# seeds.net
KiCad netlist of a schematic drawn in Altium Designer
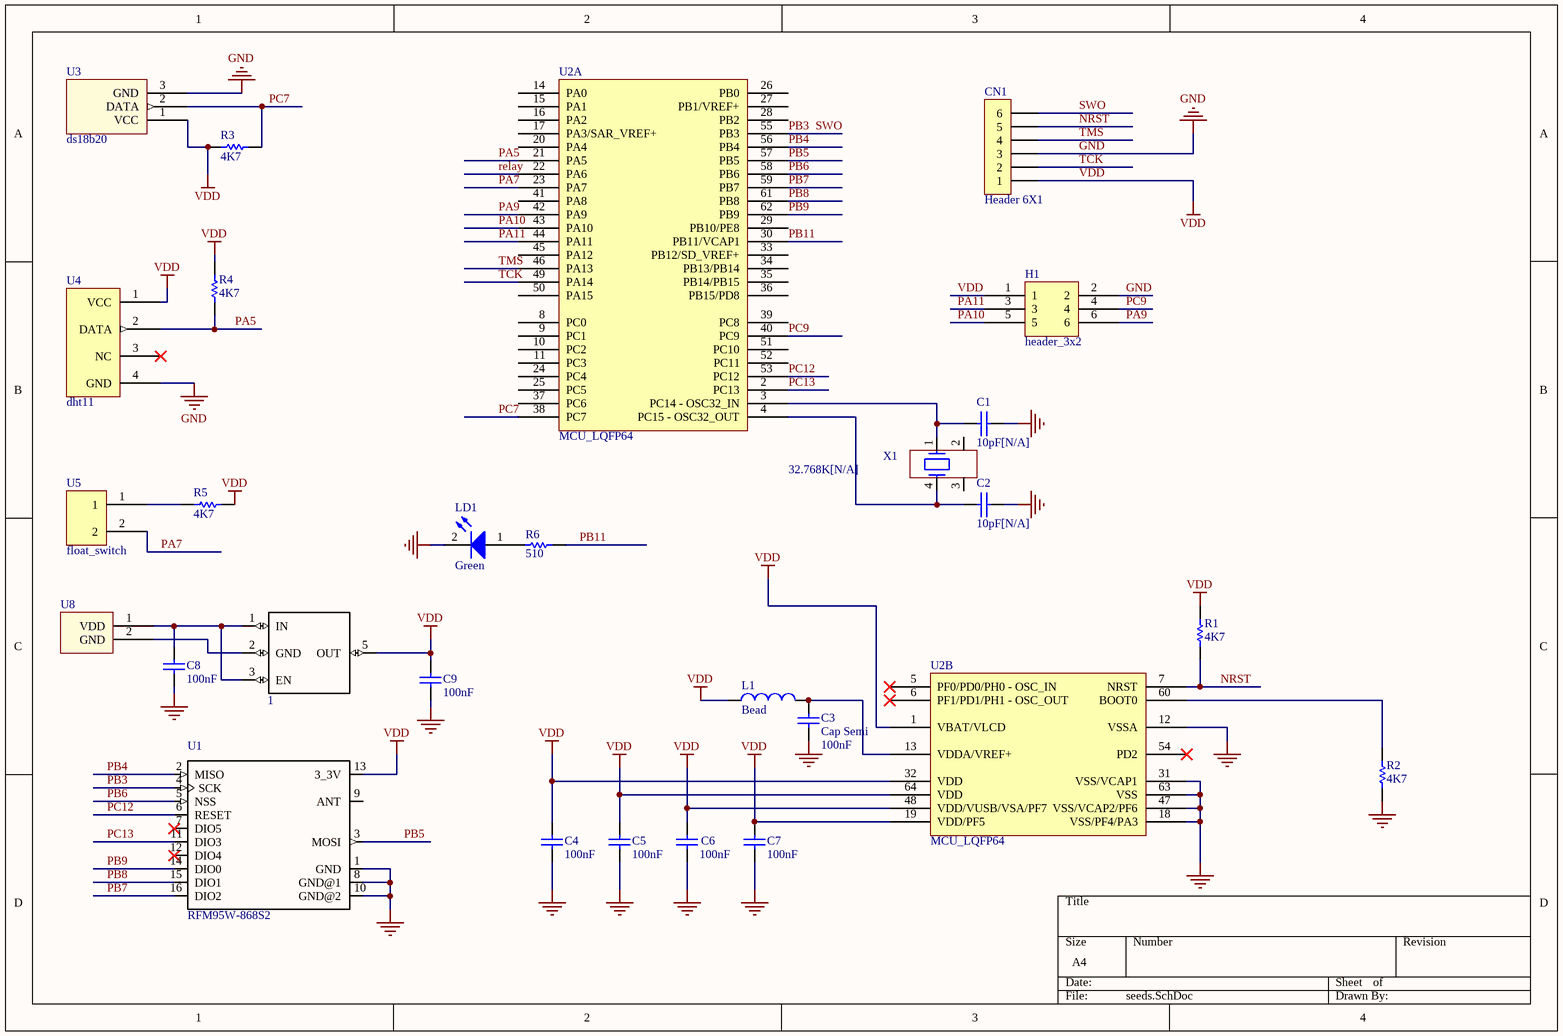
[diagram p0: seeds.SchDoc]

(export (version "E")
  (design (tool "Eeschema 10.0.6"))
  (components
    (comp (ref "1")
      (value "TLV70233DBVR")
      (footprint "SOT23-5")
      (description "LDO voltage regulator [Texas Instruments] TLV70233DBVR LDO voltage regulator")
      (fields (field (name "MF") "Texas Instruments"))
      (libsource (lib "TLV70233DBVR") (part "TLV70233DBVR"))
    )
    (comp (ref "C1")
      (value "10pF[N/A]")
      (footprint "0603C")
      (description "Capacitor")
      (libsource (lib "MB1136") (part "CAP"))
    )
    (comp (ref "C2")
      (value "10pF[N/A]")
      (footprint "0603C")
      (description "Capacitor")
      (libsource (lib "*") (part "CAP"))
    )
    (comp (ref "C3")
      (value "Cap Semi")
      (footprint "1608[0603]")
      (description "Capacitor (Semiconductor SIM Model)")
      (fields (field (name "ALTIUM_VALUE") "100nF") (field (name "PUBLISHER") "Altium Limited"))
      (libsource (lib "Miscellaneous Devices") (part "Cap Semi"))
    )
    (comp (ref "C4")
      (value "100nF")
      (footprint "0603C")
      (description "Capacitor")
      (fields (field (name "PUBLISHER") "Altium Limited"))
      (libsource (lib "Miscellaneous Devices") (part "Cap"))
    )
    (comp (ref "C5")
      (value "100nF")
      (footprint "0603C")
      (description "Capacitor")
      (fields (field (name "PUBLISHER") "Altium Limited"))
      (libsource (lib "Miscellaneous Devices") (part "Cap"))
    )
    (comp (ref "C6")
      (value "100nF")
      (footprint "0603C")
      (description "Capacitor")
      (fields (field (name "PUBLISHER") "Altium Limited"))
      (libsource (lib "Miscellaneous Devices") (part "Cap"))
    )
    (comp (ref "C7")
      (value "100nF")
      (footprint "0603C")
      (description "Capacitor")
      (fields (field (name "PUBLISHER") "Altium Limited"))
      (libsource (lib "Miscellaneous Devices") (part "Cap"))
    )
    (comp (ref "C8")
      (value "100nF")
      (footprint "0603C")
      (description "Capacitor")
      (fields (field (name "PUBLISHER") "Altium Limited"))
      (libsource (lib "Miscellaneous Devices") (part "Cap"))
    )
    (comp (ref "C9")
      (value "100nF")
      (footprint "0603C")
      (description "Capacitor")
      (fields (field (name "PUBLISHER") "Altium Limited"))
      (libsource (lib "Miscellaneous Devices") (part "Cap"))
    )
    (comp (ref "CN1")
      (value "Header 6X1")
      (footprint "1*6P")
      (description "Header, 6-Pin, Single row")
      (fields (field (name "PUBLISHER") "Altium Limited"))
      (libsource (lib "MB1136") (part "Header 6X1"))
    )
    (comp (ref "H1")
      (value "header_3x2")
      (footprint "header_3x2")
      (libsource (lib "seeds") (part "header_3x2"))
    )
    (comp (ref "L1")
      (value "Bead")
      (footprint "INDC1608L")
      (description "Inductor")
      (fields (field (name "PUBLISHER") "Altium Limited"))
      (libsource (lib "Miscellaneous Devices") (part "Inductor"))
    )
    (comp (ref "LD1")
      (value "Green")
      (footprint "0603D")
      (description "Typical RED, GREEN, YELLOW, AMBER GaAs LED")
      (fields (field (name "PUBLISHER") "Altium Limited"))
      (libsource (lib "Miscellaneous Devices") (part "LED2"))
    )
    (comp (ref "R1")
      (value "4K7")
      (footprint "0603R")
      (description "Resistor")
      (fields (field (name "PUBLISHER") "Altium Limited"))
      (libsource (lib "MB1136") (part "Res1"))
    )
    (comp (ref "R2")
      (value "4K7")
      (footprint "0603R")
      (description "Resistor")
      (fields (field (name "PUBLISHER") "Altium Limited"))
      (libsource (lib "MB1136") (part "Res1"))
    )
    (comp (ref "R3")
      (value "4K7")
      (footprint "0603R")
      (description "Resistor")
      (fields (field (name "PUBLISHER") "Altium Limited"))
      (libsource (lib "MB1136") (part "Res1"))
    )
    (comp (ref "R4")
      (value "4K7")
      (footprint "0603R")
      (description "Resistor")
      (fields (field (name "PUBLISHER") "Altium Limited"))
      (libsource (lib "MB1136") (part "Res1"))
    )
    (comp (ref "R5")
      (value "4K7")
      (footprint "0603R")
      (description "Resistor")
      (fields (field (name "PUBLISHER") "Altium Limited"))
      (libsource (lib "MB1136") (part "Res1"))
    )
    (comp (ref "R6")
      (value "510")
      (footprint "0603R")
      (description "Resistor")
      (fields (field (name "PUBLISHER") "Altium Limited"))
      (libsource (lib "Miscellaneous Devices") (part "Res1"))
    )
    (comp (ref "U1")
      (value "RFM95W-868S2")
      (footprint "XCVR_RFM95W-868S2")
      (fields (field (name "MF") "Hope Microelectronics"))
      (libsource (lib "RFM95W-868S2") (part "RFM95W-868S2"))
    )
    (comp (ref "U2") (value "MCU_LQFP64") (footprint "LQFP64") (libsource (lib "MB1136") (part "MCU_LQFP64")))
    (comp (ref "U3") (value "ds18b20") (footprint "ds18b20") (libsource (lib "seeds") (part "ds18b20")))
    (comp (ref "U4") (value "dht11") (footprint "seeds:dht11") (libsource (lib "seeds") (part "dht11")))
    (comp (ref "U5")
      (value "float_switch")
      (footprint "float_switch")
      (libsource (lib "seeds") (part "float_switch"))
    )
    (comp (ref "U8")
      (value "BATTERY_CONNECTOR")
      (footprint "BATTERY_CONNECTOR")
      (libsource (lib "seeds") (part "BATTERY_CONNECTOR"))
    )
    (comp (ref "X1") (value "32.768K[N/A]") (footprint "XTAL_4SM_8X3R8") (libsource (lib "*") (part "MC306")))
  )
  (nets
    (net (code "1") (name "/NRST") (class "Default")
      (node (ref "CN1") (pin "5") (pinfunction "5_5") (pintype "passive"))
      (node (ref "R1") (pin "1") (pinfunction "1_1") (pintype "passive"))
      (node (ref "U2") (pin "7") (pinfunction "NRST_7") (pintype "passive"))
    )
    (net (code "2") (name "/PA5") (class "Default")
      (node (ref "R4") (pin "2") (pinfunction "2_2") (pintype "passive"))
      (node (ref "U2") (pin "21") (pinfunction "PA5_21") (pintype "passive"))
      (node (ref "U4") (pin "2") (pinfunction "DATA_2") (pintype "output"))
    )
    (net (code "3") (name "/PA7") (class "Default")
      (node (ref "U2") (pin "23") (pinfunction "PA7_23") (pintype "passive"))
      (node (ref "U5") (pin "2") (pinfunction "2_2") (pintype "passive"))
    )
    (net (code "4") (name "/PA9") (class "Default")
      (node (ref "H1") (pin "6") (pinfunction "6_6") (pintype "passive"))
      (node (ref "U2") (pin "42") (pinfunction "PA9_42") (pintype "passive"))
    )
    (net (code "5") (name "/PA10") (class "Default")
      (node (ref "H1") (pin "5") (pinfunction "5_5") (pintype "passive"))
      (node (ref "U2") (pin "43") (pinfunction "PA10_43") (pintype "passive"))
    )
    (net (code "6") (name "/PA11") (class "Default")
      (node (ref "H1") (pin "3") (pinfunction "3_3") (pintype "passive"))
      (node (ref "U2") (pin "44") (pinfunction "PA11_44") (pintype "passive"))
    )
    (net (code "7") (name "/PB3") (class "Default")
      (node (ref "CN1") (pin "6") (pinfunction "6_6") (pintype "passive"))
      (node (ref "U1") (pin "4") (pinfunction "SCK_4") (pintype "input"))
      (node (ref "U2") (pin "55") (pinfunction "PB3_55") (pintype "passive"))
    )
    (net (code "8") (name "/PB4") (class "Default")
      (node (ref "U1") (pin "2") (pinfunction "MISO_2") (pintype "input"))
      (node (ref "U2") (pin "56") (pinfunction "PB4_56") (pintype "passive"))
    )
    (net (code "9") (name "/PB5") (class "Default")
      (node (ref "U1") (pin "3") (pinfunction "MOSI_3") (pintype "output"))
      (node (ref "U2") (pin "57") (pinfunction "PB5_57") (pintype "passive"))
    )
    (net (code "10") (name "/PB6") (class "Default")
      (node (ref "U1") (pin "5") (pinfunction "NSS_5") (pintype "input"))
      (node (ref "U2") (pin "58") (pinfunction "PB6_58") (pintype "passive"))
    )
    (net (code "11") (name "/PB7") (class "Default")
      (node (ref "U1") (pin "16") (pinfunction "DIO2_16") (pintype "bidirectional"))
      (node (ref "U2") (pin "59") (pinfunction "PB7_59") (pintype "passive"))
    )
    (net (code "12") (name "/PB8") (class "Default")
      (node (ref "U1") (pin "15") (pinfunction "DIO1_15") (pintype "bidirectional"))
      (node (ref "U2") (pin "61") (pinfunction "PB8_61") (pintype "passive"))
    )
    (net (code "13") (name "/PB9") (class "Default")
      (node (ref "U1") (pin "14") (pinfunction "DIO0_14") (pintype "bidirectional"))
      (node (ref "U2") (pin "62") (pinfunction "PB9_62") (pintype "passive"))
    )
    (net (code "14") (name "/PB11") (class "Default")
      (node (ref "R6") (pin "1") (pinfunction "1_1") (pintype "passive"))
      (node (ref "U2") (pin "30") (pinfunction "PB11/VCAP1_30") (pintype "passive"))
    )
    (net (code "15") (name "/PC7") (class "Default")
      (node (ref "R3") (pin "1") (pinfunction "1_1") (pintype "passive"))
      (node (ref "U2") (pin "38") (pinfunction "PC7_38") (pintype "passive"))
      (node (ref "U3") (pin "2") (pinfunction "DATA_2") (pintype "output"))
    )
    (net (code "16") (name "/PC9") (class "Default")
      (node (ref "H1") (pin "4") (pinfunction "4_4") (pintype "passive"))
      (node (ref "U2") (pin "40") (pinfunction "PC9_40") (pintype "passive"))
    )
    (net (code "17") (name "/PC12") (class "Default")
      (node (ref "U1") (pin "6") (pinfunction "RESET_6") (pintype "bidirectional"))
      (node (ref "U2") (pin "53") (pinfunction "PC12_53") (pintype "passive"))
    )
    (net (code "18") (name "/PC13") (class "Default")
      (node (ref "U1") (pin "11") (pinfunction "DIO3_11") (pintype "bidirectional"))
      (node (ref "U2") (pin "2") (pinfunction "PC13_2") (pintype "passive"))
    )
    (net (code "19") (name "/TCK") (class "Default")
      (node (ref "CN1") (pin "2") (pinfunction "2_2") (pintype "passive"))
      (node (ref "U2") (pin "49") (pinfunction "PA14_49") (pintype "passive"))
    )
    (net (code "20") (name "/TMS") (class "Default")
      (node (ref "CN1") (pin "4") (pinfunction "4_4") (pintype "passive"))
      (node (ref "U2") (pin "46") (pinfunction "PA13_46") (pintype "passive"))
    )
    (net (code "21") (name "/relay") (class "Default")
      (node (ref "U2") (pin "22") (pinfunction "PA6_22") (pintype "passive"))
    )
    (net (code "22") (name "GND") (class "Default")
      (node (ref "C1") (pin "2") (pinfunction "2_2") (pintype "passive"))
      (node (ref "C2") (pin "2") (pinfunction "2_2") (pintype "passive"))
      (node (ref "C3") (pin "2") (pinfunction "2_2") (pintype "passive"))
      (node (ref "C4") (pin "2") (pinfunction "2_2") (pintype "passive"))
      (node (ref "C5") (pin "2") (pinfunction "2_2") (pintype "passive"))
      (node (ref "C6") (pin "2") (pinfunction "2_2") (pintype "passive"))
      (node (ref "C7") (pin "2") (pinfunction "2_2") (pintype "passive"))
      (node (ref "C8") (pin "2") (pinfunction "2_2") (pintype "passive"))
      (node (ref "C9") (pin "2") (pinfunction "2_2") (pintype "passive"))
      (node (ref "CN1") (pin "3") (pinfunction "3_3") (pintype "passive"))
      (node (ref "H1") (pin "2") (pinfunction "2_2") (pintype "passive"))
      (node (ref "LD1") (pin "2") (pinfunction "K_2") (pintype "passive"))
      (node (ref "R2") (pin "1") (pinfunction "1_1") (pintype "passive"))
      (node (ref "U1") (pin "1") (pinfunction "GND_1") (pintype "power_in"))
      (node (ref "U1") (pin "10") (pinfunction "GND@2_10") (pintype "power_in"))
      (node (ref "U1") (pin "8") (pinfunction "GND@1_8") (pintype "power_in"))
      (node (ref "U2") (pin "12") (pinfunction "VSSA_12") (pintype "passive"))
      (node (ref "U2") (pin "18") (pinfunction "VSS/PF4/PA3_18") (pintype "passive"))
      (node (ref "U2") (pin "31") (pinfunction "VSS/VCAP1_31") (pintype "passive"))
      (node (ref "U2") (pin "47") (pinfunction "VSS/VCAP2/PF6_47") (pintype "passive"))
      (node (ref "U2") (pin "63") (pinfunction "VSS_63") (pintype "passive"))
      (node (ref "U3") (pin "3") (pinfunction "GND_3") (pintype "power_in"))
      (node (ref "U4") (pin "4") (pinfunction "GND_4") (pintype "power_in"))
    )
    (net (code "23") (name "Net-(1-EN)") (class "Default")
      (node (ref "1") (pin "1") (pinfunction "IN_1") (pintype "bidirectional"))
      (node (ref "1") (pin "3") (pinfunction "EN_3") (pintype "bidirectional"))
      (node (ref "C8") (pin "1") (pinfunction "1_1") (pintype "passive"))
      (node (ref "U8") (pin "1") (pinfunction "VDD_1") (pintype "power_in"))
    )
    (net (code "24") (name "Net-(1-GND)") (class "Default")
      (node (ref "1") (pin "2") (pinfunction "GND_2") (pintype "bidirectional"))
      (node (ref "U8") (pin "2") (pinfunction "GND_2") (pintype "power_in"))
    )
    (net (code "25") (name "Net-(LD1-A)") (class "Default")
      (node (ref "LD1") (pin "1") (pinfunction "A_1") (pintype "passive"))
      (node (ref "R6") (pin "2") (pinfunction "2_2") (pintype "passive"))
    )
    (net (code "26") (name "Net-(R5-Pad2)") (class "Default")
      (node (ref "R5") (pin "2") (pinfunction "2_2") (pintype "passive"))
      (node (ref "U5") (pin "1") (pinfunction "1_1") (pintype "passive"))
    )
    (net (code "27") (name "Net-(U2A-PC14_-_OSC32_IN)") (class "Default")
      (node (ref "C1") (pin "1") (pinfunction "1_1") (pintype "passive"))
      (node (ref "U2") (pin "3") (pinfunction "PC14_-_OSC32_IN_3") (pintype "passive"))
      (node (ref "X1") (pin "1") (pinfunction "1_1") (pintype "passive"))
    )
    (net (code "28") (name "Net-(U2A-PC15_-_OSC32_OUT)") (class "Default")
      (node (ref "C2") (pin "1") (pinfunction "1_1") (pintype "passive"))
      (node (ref "U2") (pin "4") (pinfunction "PC15_-_OSC32_OUT_4") (pintype "passive"))
      (node (ref "X1") (pin "4") (pinfunction "4_4") (pintype "passive"))
    )
    (net (code "29") (name "Net-(U2B-BOOT0)") (class "Default")
      (node (ref "R2") (pin "2") (pinfunction "2_2") (pintype "passive"))
      (node (ref "U2") (pin "60") (pinfunction "BOOT0_60") (pintype "passive"))
    )
    (net (code "30") (name "Net-(U2B-VDDA{slash}VREF+)") (class "Default")
      (node (ref "C3") (pin "1") (pinfunction "1_1") (pintype "passive"))
      (node (ref "L1") (pin "2") (pinfunction "2_2") (pintype "passive"))
      (node (ref "U2") (pin "13") (pinfunction "VDDA/VREF+_13") (pintype "passive"))
    )
    (net (code "31") (name "VDD") (class "Default")
      (node (ref "1") (pin "5") (pinfunction "OUT_5") (pintype "bidirectional"))
      (node (ref "C4") (pin "1") (pinfunction "1_1") (pintype "passive"))
      (node (ref "C5") (pin "1") (pinfunction "1_1") (pintype "passive"))
      (node (ref "C6") (pin "1") (pinfunction "1_1") (pintype "passive"))
      (node (ref "C7") (pin "1") (pinfunction "1_1") (pintype "passive"))
      (node (ref "C9") (pin "1") (pinfunction "1_1") (pintype "passive"))
      (node (ref "CN1") (pin "1") (pinfunction "1_1") (pintype "passive"))
      (node (ref "H1") (pin "1") (pinfunction "1_1") (pintype "passive"))
      (node (ref "L1") (pin "1") (pinfunction "1_1") (pintype "passive"))
      (node (ref "R1") (pin "2") (pinfunction "2_2") (pintype "passive"))
      (node (ref "R3") (pin "2") (pinfunction "2_2") (pintype "passive"))
      (node (ref "R4") (pin "1") (pinfunction "1_1") (pintype "passive"))
      (node (ref "R5") (pin "1") (pinfunction "1_1") (pintype "passive"))
      (node (ref "U1") (pin "13") (pinfunction "3_3V_13") (pintype "power_in"))
      (node (ref "U2") (pin "1") (pinfunction "VBAT/VLCD_1") (pintype "passive"))
      (node (ref "U2") (pin "19") (pinfunction "VDD/PF5_19") (pintype "passive"))
      (node (ref "U2") (pin "32") (pinfunction "VDD_32") (pintype "passive"))
      (node (ref "U2") (pin "48") (pinfunction "VDD/VUSB/VSA/PF7_48") (pintype "passive"))
      (node (ref "U2") (pin "64") (pinfunction "VDD_64") (pintype "passive"))
      (node (ref "U3") (pin "1") (pinfunction "VCC_1") (pintype "power_in"))
      (node (ref "U4") (pin "1") (pinfunction "VCC_1") (pintype "power_in"))
    )
    (net (code "32") (name "unconnected-(U1-ANT-Pad9)") (class "Default")
      (node (ref "U1") (pin "9") (pinfunction "ANT_9") (pintype "passive"))
    )
    (net (code "33") (name "unconnected-(U1-DIO4-Pad12)") (class "Default")
      (node (ref "U1") (pin "12") (pinfunction "DIO4_12") (pintype "bidirectional+no_connect"))
    )
    (net (code "34") (name "unconnected-(U1-DIO5-Pad7)") (class "Default")
      (node (ref "U1") (pin "7") (pinfunction "DIO5_7") (pintype "bidirectional+no_connect"))
    )
    (net (code "35") (name "unconnected-(U2A-PA0-Pad14)") (class "Default")
      (node (ref "U2") (pin "14") (pinfunction "PA0_14") (pintype "passive"))
    )
    (net (code "36") (name "unconnected-(U2A-PA1-Pad15)") (class "Default")
      (node (ref "U2") (pin "15") (pinfunction "PA1_15") (pintype "passive"))
    )
    (net (code "37") (name "unconnected-(U2A-PA2-Pad16)") (class "Default")
      (node (ref "U2") (pin "16") (pinfunction "PA2_16") (pintype "passive"))
    )
    (net (code "38") (name "unconnected-(U2A-PA3{slash}SAR_VREF+-Pad17)") (class "Default")
      (node (ref "U2") (pin "17") (pinfunction "PA3/SAR_VREF+_17") (pintype "passive"))
    )
    (net (code "39") (name "unconnected-(U2A-PA4-Pad20)") (class "Default")
      (node (ref "U2") (pin "20") (pinfunction "PA4_20") (pintype "passive"))
    )
    (net (code "40") (name "unconnected-(U2A-PA8-Pad41)") (class "Default")
      (node (ref "U2") (pin "41") (pinfunction "PA8_41") (pintype "passive"))
    )
    (net (code "41") (name "unconnected-(U2A-PA12-Pad45)") (class "Default")
      (node (ref "U2") (pin "45") (pinfunction "PA12_45") (pintype "passive"))
    )
    (net (code "42") (name "unconnected-(U2A-PA15-Pad50)") (class "Default")
      (node (ref "U2") (pin "50") (pinfunction "PA15_50") (pintype "passive"))
    )
    (net (code "43") (name "unconnected-(U2A-PB0-Pad26)") (class "Default")
      (node (ref "U2") (pin "26") (pinfunction "PB0_26") (pintype "passive"))
    )
    (net (code "44") (name "unconnected-(U2A-PB1{slash}VREF+-Pad27)") (class "Default")
      (node (ref "U2") (pin "27") (pinfunction "PB1/VREF+_27") (pintype "passive"))
    )
    (net (code "45") (name "unconnected-(U2A-PB2-Pad28)") (class "Default")
      (node (ref "U2") (pin "28") (pinfunction "PB2_28") (pintype "passive"))
    )
    (net (code "46") (name "unconnected-(U2A-PB10{slash}PE8-Pad29)") (class "Default")
      (node (ref "U2") (pin "29") (pinfunction "PB10/PE8_29") (pintype "passive"))
    )
    (net (code "47") (name "unconnected-(U2A-PB12{slash}SD_VREF+-Pad33)") (class "Default")
      (node (ref "U2") (pin "33") (pinfunction "PB12/SD_VREF+_33") (pintype "passive"))
    )
    (net (code "48") (name "unconnected-(U2A-PB13{slash}PB14-Pad34)") (class "Default")
      (node (ref "U2") (pin "34") (pinfunction "PB13/PB14_34") (pintype "passive"))
    )
    (net (code "49") (name "unconnected-(U2A-PB14{slash}PB15-Pad35)") (class "Default")
      (node (ref "U2") (pin "35") (pinfunction "PB14/PB15_35") (pintype "passive"))
    )
    (net (code "50") (name "unconnected-(U2A-PB15{slash}PD8-Pad36)") (class "Default")
      (node (ref "U2") (pin "36") (pinfunction "PB15/PD8_36") (pintype "passive"))
    )
    (net (code "51") (name "unconnected-(U2A-PC0-Pad8)") (class "Default")
      (node (ref "U2") (pin "8") (pinfunction "PC0_8") (pintype "passive"))
    )
    (net (code "52") (name "unconnected-(U2A-PC1-Pad9)") (class "Default")
      (node (ref "U2") (pin "9") (pinfunction "PC1_9") (pintype "passive"))
    )
    (net (code "53") (name "unconnected-(U2A-PC2-Pad10)") (class "Default")
      (node (ref "U2") (pin "10") (pinfunction "PC2_10") (pintype "passive"))
    )
    (net (code "54") (name "unconnected-(U2A-PC3-Pad11)") (class "Default")
      (node (ref "U2") (pin "11") (pinfunction "PC3_11") (pintype "passive"))
    )
    (net (code "55") (name "unconnected-(U2A-PC4-Pad24)") (class "Default")
      (node (ref "U2") (pin "24") (pinfunction "PC4_24") (pintype "passive"))
    )
    (net (code "56") (name "unconnected-(U2A-PC5-Pad25)") (class "Default")
      (node (ref "U2") (pin "25") (pinfunction "PC5_25") (pintype "passive"))
    )
    (net (code "57") (name "unconnected-(U2A-PC6-Pad37)") (class "Default")
      (node (ref "U2") (pin "37") (pinfunction "PC6_37") (pintype "passive"))
    )
    (net (code "58") (name "unconnected-(U2A-PC8-Pad39)") (class "Default")
      (node (ref "U2") (pin "39") (pinfunction "PC8_39") (pintype "passive"))
    )
    (net (code "59") (name "unconnected-(U2A-PC10-Pad51)") (class "Default")
      (node (ref "U2") (pin "51") (pinfunction "PC10_51") (pintype "passive"))
    )
    (net (code "60") (name "unconnected-(U2A-PC11-Pad52)") (class "Default")
      (node (ref "U2") (pin "52") (pinfunction "PC11_52") (pintype "passive"))
    )
    (net (code "61") (name "unconnected-(U2B-PD2-Pad54)") (class "Default")
      (node (ref "U2") (pin "54") (pinfunction "PD2_54") (pintype "passive+no_connect"))
    )
    (net (code "62") (name "unconnected-(U2B-PF0{slash}PD0{slash}PH0_-_OSC_IN-Pad5)") (class "Default")
      (node (ref "U2") (pin "5") (pinfunction "PF0/PD0/PH0_-_OSC_IN_5") (pintype "passive+no_connect"))
    )
    (net (code "63") (name "unconnected-(U2B-PF1{slash}PD1{slash}PH1_-_OSC_OUT-Pad6)") (class "Default")
      (node (ref "U2") (pin "6") (pinfunction "PF1/PD1/PH1_-_OSC_OUT_6") (pintype "passive+no_connect"))
    )
    (net (code "64") (name "unconnected-(U4-NC-Pad3)") (class "Default")
      (node (ref "U4") (pin "3") (pinfunction "NC_3") (pintype "passive+no_connect"))
    )
    (net (code "65") (name "unconnected-(X1-Pad2)") (class "Default")
      (node (ref "X1") (pin "2") (pinfunction "2_2") (pintype "passive"))
    )
    (net (code "66") (name "unconnected-(X1-Pad3)") (class "Default")
      (node (ref "X1") (pin "3") (pinfunction "3_3") (pintype "passive"))
    )
  )
)
